# MCP23017_I16_v1_0.net
KiCad netlist of a schematic drawn in EAGLE
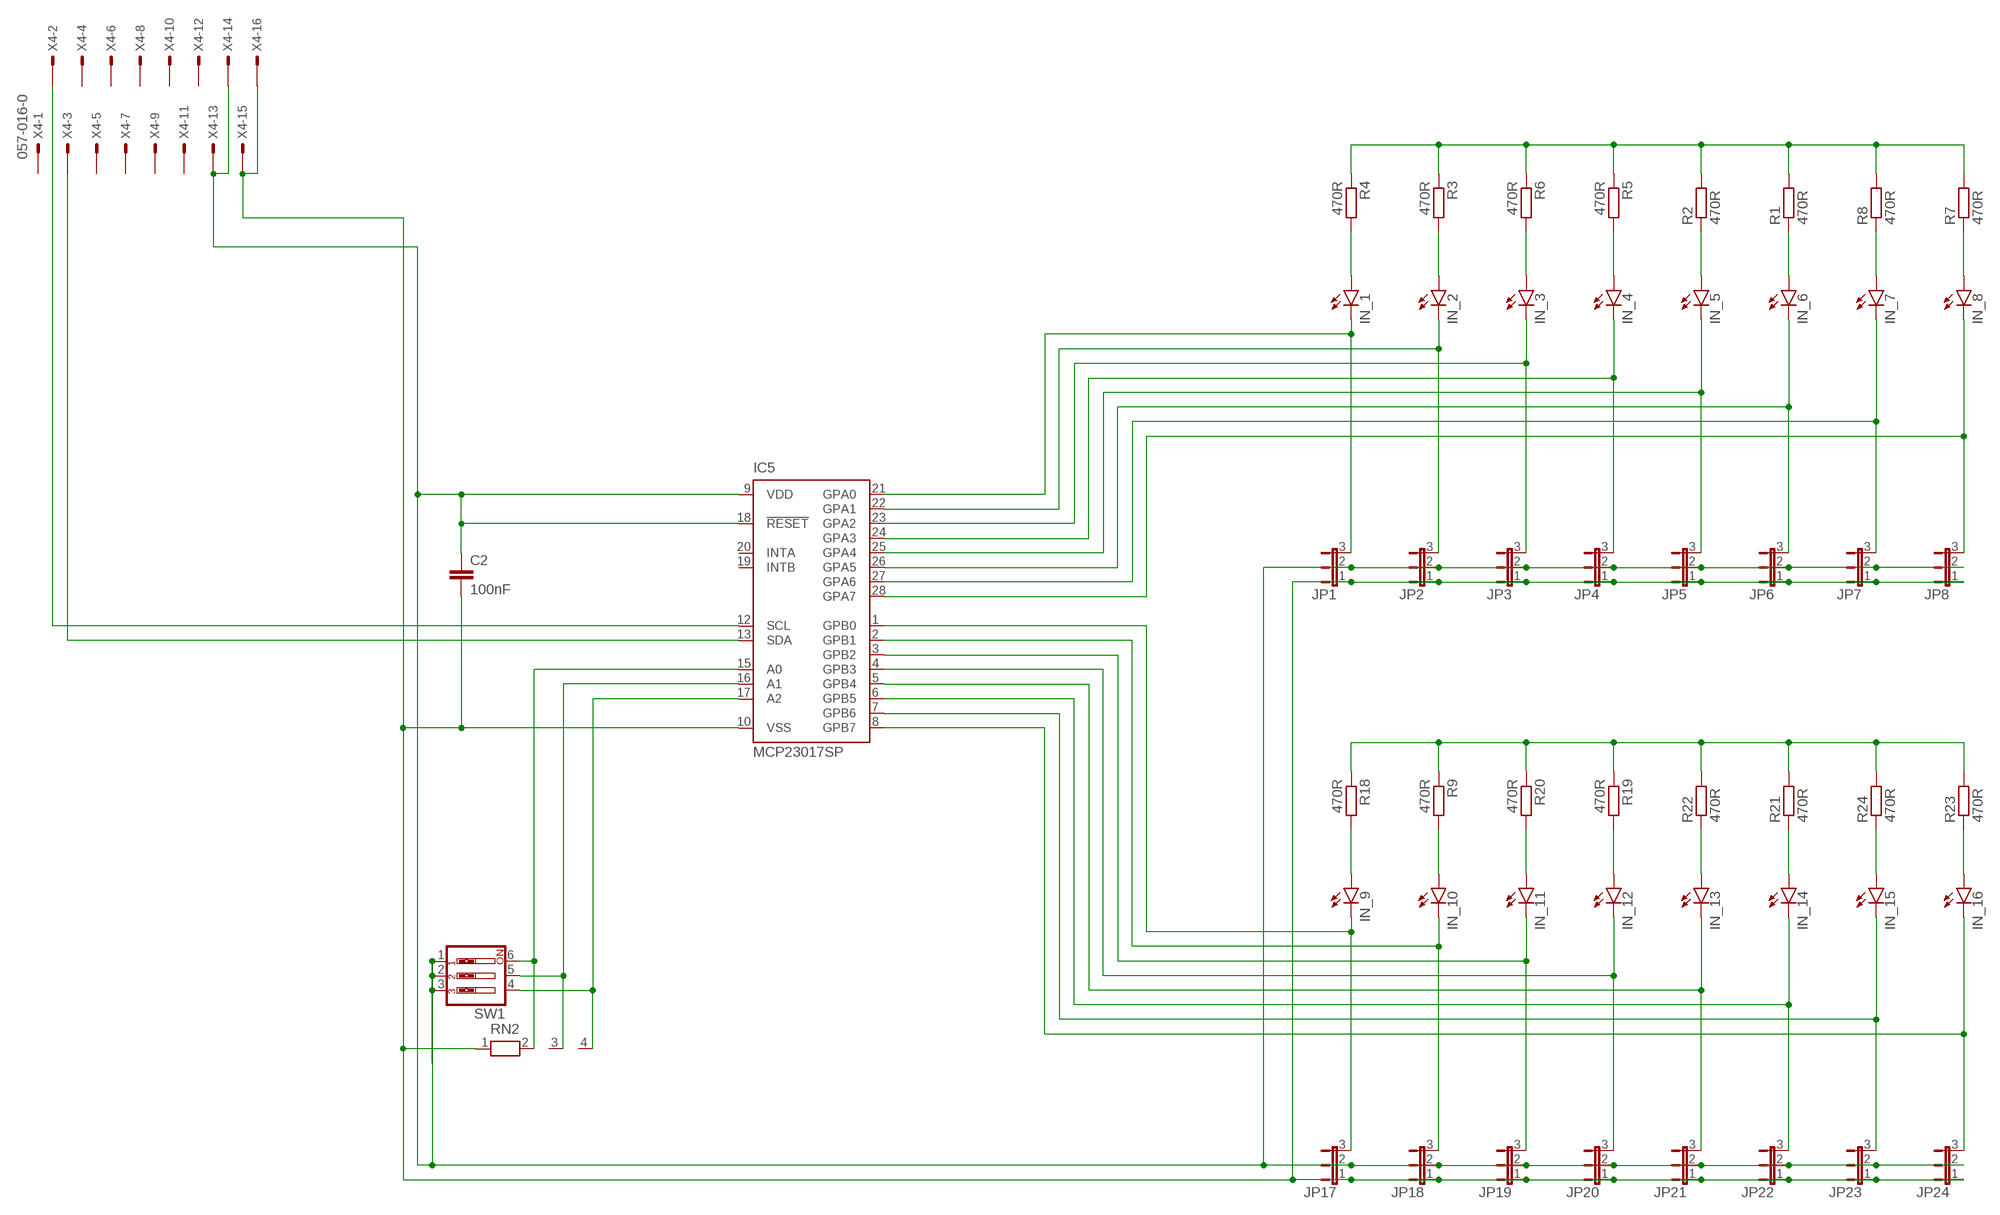
[diagram p0: schematic, sheet 1]

(export (version "E")
  (design (tool "Eeschema 10.0.6"))
  (components
    (comp (ref "C2")
      (value "100nF")
      (footprint "eagle-import:C025-024X044")
      (libsource (lib "eagle-import") (part "C-EU025-024X044"))
    )
    (comp (ref "IC5")
      (value "MCP23017SP")
      (footprint "eagle-import:DIL28-3")
      (libsource (lib "eagle-import") (part "MCP23017SP"))
    )
    (comp (ref "IN_1")
      (value "LED3MM")
      (footprint "eagle-import:LED3MM")
      (libsource (lib "eagle-import") (part "LED3MM"))
    )
    (comp (ref "IN_2")
      (value "LED3MM")
      (footprint "eagle-import:LED3MM")
      (libsource (lib "eagle-import") (part "LED3MM"))
    )
    (comp (ref "IN_3")
      (value "LED3MM")
      (footprint "eagle-import:LED3MM")
      (libsource (lib "eagle-import") (part "LED3MM"))
    )
    (comp (ref "IN_4")
      (value "LED3MM")
      (footprint "eagle-import:LED3MM")
      (libsource (lib "eagle-import") (part "LED3MM"))
    )
    (comp (ref "IN_5")
      (value "LED3MM")
      (footprint "eagle-import:LED3MM")
      (libsource (lib "eagle-import") (part "LED3MM"))
    )
    (comp (ref "IN_6")
      (value "LED3MM")
      (footprint "eagle-import:LED3MM")
      (libsource (lib "eagle-import") (part "LED3MM"))
    )
    (comp (ref "IN_7")
      (value "LED3MM")
      (footprint "eagle-import:LED3MM")
      (libsource (lib "eagle-import") (part "LED3MM"))
    )
    (comp (ref "IN_8")
      (value "LED3MM")
      (footprint "eagle-import:LED3MM")
      (libsource (lib "eagle-import") (part "LED3MM"))
    )
    (comp (ref "IN_9")
      (value "LED3MM")
      (footprint "eagle-import:LED3MM")
      (libsource (lib "eagle-import") (part "LED3MM"))
    )
    (comp (ref "IN_10")
      (value "LED3MM")
      (footprint "eagle-import:LED3MM")
      (libsource (lib "eagle-import") (part "LED3MM"))
    )
    (comp (ref "IN_11")
      (value "LED3MM")
      (footprint "eagle-import:LED3MM")
      (libsource (lib "eagle-import") (part "LED3MM"))
    )
    (comp (ref "IN_12")
      (value "LED3MM")
      (footprint "eagle-import:LED3MM")
      (libsource (lib "eagle-import") (part "LED3MM"))
    )
    (comp (ref "IN_13")
      (value "LED3MM")
      (footprint "eagle-import:LED3MM")
      (libsource (lib "eagle-import") (part "LED3MM"))
    )
    (comp (ref "IN_14")
      (value "LED3MM")
      (footprint "eagle-import:LED3MM")
      (libsource (lib "eagle-import") (part "LED3MM"))
    )
    (comp (ref "IN_15")
      (value "LED3MM")
      (footprint "eagle-import:LED3MM")
      (libsource (lib "eagle-import") (part "LED3MM"))
    )
    (comp (ref "IN_16")
      (value "LED3MM")
      (footprint "eagle-import:LED3MM")
      (libsource (lib "eagle-import") (part "LED3MM"))
    )
    (comp (ref "JP1")
      (value "JP2E")
      (footprint "eagle-import:JP2")
      (libsource (lib "eagle-import") (part "JP2E"))
    )
    (comp (ref "JP2")
      (value "JP2E")
      (footprint "eagle-import:JP2")
      (libsource (lib "eagle-import") (part "JP2E"))
    )
    (comp (ref "JP3")
      (value "JP2E")
      (footprint "eagle-import:JP2")
      (libsource (lib "eagle-import") (part "JP2E"))
    )
    (comp (ref "JP4")
      (value "JP2E")
      (footprint "eagle-import:JP2")
      (libsource (lib "eagle-import") (part "JP2E"))
    )
    (comp (ref "JP5")
      (value "JP2E")
      (footprint "eagle-import:JP2")
      (libsource (lib "eagle-import") (part "JP2E"))
    )
    (comp (ref "JP6")
      (value "JP2E")
      (footprint "eagle-import:JP2")
      (libsource (lib "eagle-import") (part "JP2E"))
    )
    (comp (ref "JP7")
      (value "JP2E")
      (footprint "eagle-import:JP2")
      (libsource (lib "eagle-import") (part "JP2E"))
    )
    (comp (ref "JP8")
      (value "JP2E")
      (footprint "eagle-import:JP2")
      (libsource (lib "eagle-import") (part "JP2E"))
    )
    (comp (ref "JP17")
      (value "JP2E")
      (footprint "eagle-import:JP2")
      (libsource (lib "eagle-import") (part "JP2E"))
    )
    (comp (ref "JP18")
      (value "JP2E")
      (footprint "eagle-import:JP2")
      (libsource (lib "eagle-import") (part "JP2E"))
    )
    (comp (ref "JP19")
      (value "JP2E")
      (footprint "eagle-import:JP2")
      (libsource (lib "eagle-import") (part "JP2E"))
    )
    (comp (ref "JP20")
      (value "JP2E")
      (footprint "eagle-import:JP2")
      (libsource (lib "eagle-import") (part "JP2E"))
    )
    (comp (ref "JP21")
      (value "JP2E")
      (footprint "eagle-import:JP2")
      (libsource (lib "eagle-import") (part "JP2E"))
    )
    (comp (ref "JP22")
      (value "JP2E")
      (footprint "eagle-import:JP2")
      (libsource (lib "eagle-import") (part "JP2E"))
    )
    (comp (ref "JP23")
      (value "JP2E")
      (footprint "eagle-import:JP2")
      (libsource (lib "eagle-import") (part "JP2E"))
    )
    (comp (ref "JP24")
      (value "JP2E")
      (footprint "eagle-import:JP2")
      (libsource (lib "eagle-import") (part "JP2E"))
    )
    (comp (ref "R1")
      (value "470R")
      (footprint "eagle-import:0309_10")
      (libsource (lib "eagle-import") (part "R-EU_0309/10"))
    )
    (comp (ref "R2")
      (value "470R")
      (footprint "eagle-import:0309_10")
      (libsource (lib "eagle-import") (part "R-EU_0309/10"))
    )
    (comp (ref "R3")
      (value "470R")
      (footprint "eagle-import:0309_10")
      (libsource (lib "eagle-import") (part "R-EU_0309/10"))
    )
    (comp (ref "R4")
      (value "470R")
      (footprint "eagle-import:0309_10")
      (libsource (lib "eagle-import") (part "R-EU_0309/10"))
    )
    (comp (ref "R5")
      (value "470R")
      (footprint "eagle-import:0309_10")
      (libsource (lib "eagle-import") (part "R-EU_0309/10"))
    )
    (comp (ref "R6")
      (value "470R")
      (footprint "eagle-import:0309_10")
      (libsource (lib "eagle-import") (part "R-EU_0309/10"))
    )
    (comp (ref "R7")
      (value "470R")
      (footprint "eagle-import:0309_10")
      (libsource (lib "eagle-import") (part "R-EU_0309/10"))
    )
    (comp (ref "R8")
      (value "470R")
      (footprint "eagle-import:0309_10")
      (libsource (lib "eagle-import") (part "R-EU_0309/10"))
    )
    (comp (ref "R9")
      (value "470R")
      (footprint "eagle-import:0309_10")
      (libsource (lib "eagle-import") (part "R-EU_0309/10"))
    )
    (comp (ref "R18")
      (value "470R")
      (footprint "eagle-import:0309_10")
      (libsource (lib "eagle-import") (part "R-EU_0309/10"))
    )
    (comp (ref "R19")
      (value "470R")
      (footprint "eagle-import:0309_10")
      (libsource (lib "eagle-import") (part "R-EU_0309/10"))
    )
    (comp (ref "R20")
      (value "470R")
      (footprint "eagle-import:0309_10")
      (libsource (lib "eagle-import") (part "R-EU_0309/10"))
    )
    (comp (ref "R21")
      (value "470R")
      (footprint "eagle-import:0309_10")
      (libsource (lib "eagle-import") (part "R-EU_0309/10"))
    )
    (comp (ref "R22")
      (value "470R")
      (footprint "eagle-import:0309_10")
      (libsource (lib "eagle-import") (part "R-EU_0309/10"))
    )
    (comp (ref "R23")
      (value "470R")
      (footprint "eagle-import:0309_10")
      (libsource (lib "eagle-import") (part "R-EU_0309/10"))
    )
    (comp (ref "R24")
      (value "470R")
      (footprint "eagle-import:0309_10")
      (libsource (lib "eagle-import") (part "R-EU_0309/10"))
    )
    (comp (ref "RN2")
      (value "RN03")
      (footprint "eagle-import:RN-3")
      (libsource (lib "eagle-import") (part "RN03"))
    )
    (comp (ref "SW1")
      (value "SW_DIP-3")
      (footprint "eagle-import:EDG-03")
      (libsource (lib "eagle-import") (part "SW_DIP-3"))
    )
    (comp (ref "X4")
      (value "057-016-0")
      (footprint "eagle-import:057-016-0")
      (libsource (lib "eagle-import") (part "057-016-0"))
    )
  )
  (nets
    (net (code "1") (name "/VCC5.2") (class "Default")
      (node (ref "C2") (pin "1") (pinfunction "1_1") (pintype "passive"))
      (node (ref "IC5") (pin "18") (pinfunction "~{RESET}_18") (pintype "input"))
      (node (ref "IC5") (pin "9") (pinfunction "VDD_9") (pintype "power_in"))
      (node (ref "JP1") (pin "2") (pinfunction "2_2") (pintype "passive"))
      (node (ref "JP17") (pin "2") (pinfunction "2_2") (pintype "passive"))
      (node (ref "JP18") (pin "2") (pinfunction "2_2") (pintype "passive"))
      (node (ref "JP19") (pin "2") (pinfunction "2_2") (pintype "passive"))
      (node (ref "JP2") (pin "2") (pinfunction "2_2") (pintype "passive"))
      (node (ref "JP20") (pin "2") (pinfunction "2_2") (pintype "passive"))
      (node (ref "JP21") (pin "2") (pinfunction "2_2") (pintype "passive"))
      (node (ref "JP22") (pin "2") (pinfunction "2_2") (pintype "passive"))
      (node (ref "JP23") (pin "2") (pinfunction "2_2") (pintype "passive"))
      (node (ref "JP24") (pin "2") (pinfunction "2_2") (pintype "passive"))
      (node (ref "JP3") (pin "2") (pinfunction "2_2") (pintype "passive"))
      (node (ref "JP4") (pin "2") (pinfunction "2_2") (pintype "passive"))
      (node (ref "JP5") (pin "2") (pinfunction "2_2") (pintype "passive"))
      (node (ref "JP6") (pin "2") (pinfunction "2_2") (pintype "passive"))
      (node (ref "JP7") (pin "2") (pinfunction "2_2") (pintype "passive"))
      (node (ref "JP8") (pin "2") (pinfunction "2_2") (pintype "passive"))
      (node (ref "R1") (pin "2") (pinfunction "2_2") (pintype "passive"))
      (node (ref "R18") (pin "1") (pinfunction "1_1") (pintype "passive"))
      (node (ref "R19") (pin "1") (pinfunction "1_1") (pintype "passive"))
      (node (ref "R2") (pin "2") (pinfunction "2_2") (pintype "passive"))
      (node (ref "R20") (pin "1") (pinfunction "1_1") (pintype "passive"))
      (node (ref "R21") (pin "2") (pinfunction "2_2") (pintype "passive"))
      (node (ref "R22") (pin "2") (pinfunction "2_2") (pintype "passive"))
      (node (ref "R23") (pin "2") (pinfunction "2_2") (pintype "passive"))
      (node (ref "R24") (pin "2") (pinfunction "2_2") (pintype "passive"))
      (node (ref "R3") (pin "1") (pinfunction "1_1") (pintype "passive"))
      (node (ref "R4") (pin "1") (pinfunction "1_1") (pintype "passive"))
      (node (ref "R5") (pin "1") (pinfunction "1_1") (pintype "passive"))
      (node (ref "R6") (pin "1") (pinfunction "1_1") (pintype "passive"))
      (node (ref "R7") (pin "2") (pinfunction "2_2") (pintype "passive"))
      (node (ref "R8") (pin "2") (pinfunction "2_2") (pintype "passive"))
      (node (ref "R9") (pin "1") (pinfunction "1_1") (pintype "passive"))
      (node (ref "SW1") (pin "1") (pinfunction "1_1") (pintype "passive"))
      (node (ref "SW1") (pin "2") (pinfunction "2_2") (pintype "passive"))
      (node (ref "SW1") (pin "3") (pinfunction "3_3") (pintype "passive"))
      (node (ref "X4") (pin "13") (pinfunction "S_13") (pintype "passive"))
      (node (ref "X4") (pin "14") (pinfunction "S_14") (pintype "passive"))
    )
    (net (code "2") (name "Net-(IC5-A0)") (class "Default")
      (node (ref "IC5") (pin "15") (pinfunction "A0_15") (pintype "input"))
      (node (ref "RN2") (pin "2") (pinfunction "2_2") (pintype "passive"))
      (node (ref "SW1") (pin "6") (pinfunction "6_6") (pintype "passive"))
    )
    (net (code "3") (name "Net-(IC5-A1)") (class "Default")
      (node (ref "IC5") (pin "16") (pinfunction "A1_16") (pintype "input"))
      (node (ref "RN2") (pin "3") (pinfunction "3_3") (pintype "passive"))
      (node (ref "SW1") (pin "5") (pinfunction "5_5") (pintype "passive"))
    )
    (net (code "4") (name "Net-(IC5-A2)") (class "Default")
      (node (ref "IC5") (pin "17") (pinfunction "A2_17") (pintype "input"))
      (node (ref "RN2") (pin "4") (pinfunction "4_4") (pintype "passive"))
      (node (ref "SW1") (pin "4") (pinfunction "4_4") (pintype "passive"))
    )
    (net (code "5") (name "Net-(IC5-GPA0)") (class "Default")
      (node (ref "IC5") (pin "21") (pinfunction "GPA0_21") (pintype "bidirectional"))
      (node (ref "IN_1") (pin "K") (pinfunction "C_K") (pintype "passive"))
      (node (ref "JP1") (pin "3") (pinfunction "3_3") (pintype "passive"))
    )
    (net (code "6") (name "Net-(IC5-GPA1)") (class "Default")
      (node (ref "IC5") (pin "22") (pinfunction "GPA1_22") (pintype "bidirectional"))
      (node (ref "IN_2") (pin "K") (pinfunction "C_K") (pintype "passive"))
      (node (ref "JP2") (pin "3") (pinfunction "3_3") (pintype "passive"))
    )
    (net (code "7") (name "Net-(IC5-GPA2)") (class "Default")
      (node (ref "IC5") (pin "23") (pinfunction "GPA2_23") (pintype "bidirectional"))
      (node (ref "IN_3") (pin "K") (pinfunction "C_K") (pintype "passive"))
      (node (ref "JP3") (pin "3") (pinfunction "3_3") (pintype "passive"))
    )
    (net (code "8") (name "Net-(IC5-GPA3)") (class "Default")
      (node (ref "IC5") (pin "24") (pinfunction "GPA3_24") (pintype "bidirectional"))
      (node (ref "IN_4") (pin "K") (pinfunction "C_K") (pintype "passive"))
      (node (ref "JP4") (pin "3") (pinfunction "3_3") (pintype "passive"))
    )
    (net (code "9") (name "Net-(IC5-GPA4)") (class "Default")
      (node (ref "IC5") (pin "25") (pinfunction "GPA4_25") (pintype "bidirectional"))
      (node (ref "IN_5") (pin "K") (pinfunction "C_K") (pintype "passive"))
      (node (ref "JP5") (pin "3") (pinfunction "3_3") (pintype "passive"))
    )
    (net (code "10") (name "Net-(IC5-GPA5)") (class "Default")
      (node (ref "IC5") (pin "26") (pinfunction "GPA5_26") (pintype "bidirectional"))
      (node (ref "IN_6") (pin "K") (pinfunction "C_K") (pintype "passive"))
      (node (ref "JP6") (pin "3") (pinfunction "3_3") (pintype "passive"))
    )
    (net (code "11") (name "Net-(IC5-GPA6)") (class "Default")
      (node (ref "IC5") (pin "27") (pinfunction "GPA6_27") (pintype "bidirectional"))
      (node (ref "IN_7") (pin "K") (pinfunction "C_K") (pintype "passive"))
      (node (ref "JP7") (pin "3") (pinfunction "3_3") (pintype "passive"))
    )
    (net (code "12") (name "Net-(IC5-GPA7)") (class "Default")
      (node (ref "IC5") (pin "28") (pinfunction "GPA7_28") (pintype "bidirectional"))
      (node (ref "IN_8") (pin "K") (pinfunction "C_K") (pintype "passive"))
      (node (ref "JP8") (pin "3") (pinfunction "3_3") (pintype "passive"))
    )
    (net (code "13") (name "Net-(IC5-GPB0)") (class "Default")
      (node (ref "IC5") (pin "1") (pinfunction "GPB0_1") (pintype "bidirectional"))
      (node (ref "IN_9") (pin "K") (pinfunction "C_K") (pintype "passive"))
      (node (ref "JP17") (pin "3") (pinfunction "3_3") (pintype "passive"))
    )
    (net (code "14") (name "Net-(IC5-GPB1)") (class "Default")
      (node (ref "IC5") (pin "2") (pinfunction "GPB1_2") (pintype "bidirectional"))
      (node (ref "IN_10") (pin "K") (pinfunction "C_K") (pintype "passive"))
      (node (ref "JP18") (pin "3") (pinfunction "3_3") (pintype "passive"))
    )
    (net (code "15") (name "Net-(IC5-GPB2)") (class "Default")
      (node (ref "IC5") (pin "3") (pinfunction "GPB2_3") (pintype "bidirectional"))
      (node (ref "IN_11") (pin "K") (pinfunction "C_K") (pintype "passive"))
      (node (ref "JP19") (pin "3") (pinfunction "3_3") (pintype "passive"))
    )
    (net (code "16") (name "Net-(IC5-GPB3)") (class "Default")
      (node (ref "IC5") (pin "4") (pinfunction "GPB3_4") (pintype "bidirectional"))
      (node (ref "IN_12") (pin "K") (pinfunction "C_K") (pintype "passive"))
      (node (ref "JP20") (pin "3") (pinfunction "3_3") (pintype "passive"))
    )
    (net (code "17") (name "Net-(IC5-GPB4)") (class "Default")
      (node (ref "IC5") (pin "5") (pinfunction "GPB4_5") (pintype "bidirectional"))
      (node (ref "IN_13") (pin "K") (pinfunction "C_K") (pintype "passive"))
      (node (ref "JP21") (pin "3") (pinfunction "3_3") (pintype "passive"))
    )
    (net (code "18") (name "Net-(IC5-GPB5)") (class "Default")
      (node (ref "IC5") (pin "6") (pinfunction "GPB5_6") (pintype "bidirectional"))
      (node (ref "IN_14") (pin "K") (pinfunction "C_K") (pintype "passive"))
      (node (ref "JP22") (pin "3") (pinfunction "3_3") (pintype "passive"))
    )
    (net (code "19") (name "Net-(IC5-GPB6)") (class "Default")
      (node (ref "IC5") (pin "7") (pinfunction "GPB6_7") (pintype "bidirectional"))
      (node (ref "IN_15") (pin "K") (pinfunction "C_K") (pintype "passive"))
      (node (ref "JP23") (pin "3") (pinfunction "3_3") (pintype "passive"))
    )
    (net (code "20") (name "Net-(IC5-GPB7)") (class "Default")
      (node (ref "IC5") (pin "8") (pinfunction "GPB7_8") (pintype "bidirectional"))
      (node (ref "IN_16") (pin "K") (pinfunction "C_K") (pintype "passive"))
      (node (ref "JP24") (pin "3") (pinfunction "3_3") (pintype "passive"))
    )
    (net (code "21") (name "Net-(IC5-SCL)") (class "Default")
      (node (ref "IC5") (pin "12") (pinfunction "SCL_12") (pintype "input"))
      (node (ref "X4") (pin "2") (pinfunction "S_2") (pintype "passive"))
    )
    (net (code "22") (name "Net-(IC5-SDA)") (class "Default")
      (node (ref "IC5") (pin "13") (pinfunction "SDA_13") (pintype "bidirectional"))
      (node (ref "X4") (pin "3") (pinfunction "S_3") (pintype "passive"))
    )
    (net (code "23") (name "Net-(IC5-VSS)") (class "Default")
      (node (ref "C2") (pin "2") (pinfunction "2_2") (pintype "passive"))
      (node (ref "IC5") (pin "10") (pinfunction "VSS_10") (pintype "power_in"))
      (node (ref "JP1") (pin "1") (pinfunction "1_1") (pintype "passive"))
      (node (ref "JP17") (pin "1") (pinfunction "1_1") (pintype "passive"))
      (node (ref "JP18") (pin "1") (pinfunction "1_1") (pintype "passive"))
      (node (ref "JP19") (pin "1") (pinfunction "1_1") (pintype "passive"))
      (node (ref "JP2") (pin "1") (pinfunction "1_1") (pintype "passive"))
      (node (ref "JP20") (pin "1") (pinfunction "1_1") (pintype "passive"))
      (node (ref "JP21") (pin "1") (pinfunction "1_1") (pintype "passive"))
      (node (ref "JP22") (pin "1") (pinfunction "1_1") (pintype "passive"))
      (node (ref "JP23") (pin "1") (pinfunction "1_1") (pintype "passive"))
      (node (ref "JP24") (pin "1") (pinfunction "1_1") (pintype "passive"))
      (node (ref "JP3") (pin "1") (pinfunction "1_1") (pintype "passive"))
      (node (ref "JP4") (pin "1") (pinfunction "1_1") (pintype "passive"))
      (node (ref "JP5") (pin "1") (pinfunction "1_1") (pintype "passive"))
      (node (ref "JP6") (pin "1") (pinfunction "1_1") (pintype "passive"))
      (node (ref "JP7") (pin "1") (pinfunction "1_1") (pintype "passive"))
      (node (ref "JP8") (pin "1") (pinfunction "1_1") (pintype "passive"))
      (node (ref "RN2") (pin "1") (pinfunction "1_1") (pintype "passive"))
      (node (ref "X4") (pin "15") (pinfunction "S_15") (pintype "passive"))
      (node (ref "X4") (pin "16") (pinfunction "S_16") (pintype "passive"))
    )
    (net (code "24") (name "Net-(IN_1-PadA)") (class "Default")
      (node (ref "IN_1") (pin "A") (pinfunction "A_A") (pintype "passive"))
      (node (ref "R4") (pin "2") (pinfunction "2_2") (pintype "passive"))
    )
    (net (code "25") (name "Net-(IN_2-PadA)") (class "Default")
      (node (ref "IN_2") (pin "A") (pinfunction "A_A") (pintype "passive"))
      (node (ref "R3") (pin "2") (pinfunction "2_2") (pintype "passive"))
    )
    (net (code "26") (name "Net-(IN_3-PadA)") (class "Default")
      (node (ref "IN_3") (pin "A") (pinfunction "A_A") (pintype "passive"))
      (node (ref "R6") (pin "2") (pinfunction "2_2") (pintype "passive"))
    )
    (net (code "27") (name "Net-(IN_4-PadA)") (class "Default")
      (node (ref "IN_4") (pin "A") (pinfunction "A_A") (pintype "passive"))
      (node (ref "R5") (pin "2") (pinfunction "2_2") (pintype "passive"))
    )
    (net (code "28") (name "Net-(IN_5-PadA)") (class "Default")
      (node (ref "IN_5") (pin "A") (pinfunction "A_A") (pintype "passive"))
      (node (ref "R2") (pin "1") (pinfunction "1_1") (pintype "passive"))
    )
    (net (code "29") (name "Net-(IN_6-PadA)") (class "Default")
      (node (ref "IN_6") (pin "A") (pinfunction "A_A") (pintype "passive"))
      (node (ref "R1") (pin "1") (pinfunction "1_1") (pintype "passive"))
    )
    (net (code "30") (name "Net-(IN_7-PadA)") (class "Default")
      (node (ref "IN_7") (pin "A") (pinfunction "A_A") (pintype "passive"))
      (node (ref "R8") (pin "1") (pinfunction "1_1") (pintype "passive"))
    )
    (net (code "31") (name "Net-(IN_8-PadA)") (class "Default")
      (node (ref "IN_8") (pin "A") (pinfunction "A_A") (pintype "passive"))
      (node (ref "R7") (pin "1") (pinfunction "1_1") (pintype "passive"))
    )
    (net (code "32") (name "Net-(IN_9-PadA)") (class "Default")
      (node (ref "IN_9") (pin "A") (pinfunction "A_A") (pintype "passive"))
      (node (ref "R18") (pin "2") (pinfunction "2_2") (pintype "passive"))
    )
    (net (code "33") (name "Net-(IN_10-PadA)") (class "Default")
      (node (ref "IN_10") (pin "A") (pinfunction "A_A") (pintype "passive"))
      (node (ref "R9") (pin "2") (pinfunction "2_2") (pintype "passive"))
    )
    (net (code "34") (name "Net-(IN_11-PadA)") (class "Default")
      (node (ref "IN_11") (pin "A") (pinfunction "A_A") (pintype "passive"))
      (node (ref "R20") (pin "2") (pinfunction "2_2") (pintype "passive"))
    )
    (net (code "35") (name "Net-(IN_12-PadA)") (class "Default")
      (node (ref "IN_12") (pin "A") (pinfunction "A_A") (pintype "passive"))
      (node (ref "R19") (pin "2") (pinfunction "2_2") (pintype "passive"))
    )
    (net (code "36") (name "Net-(IN_13-PadA)") (class "Default")
      (node (ref "IN_13") (pin "A") (pinfunction "A_A") (pintype "passive"))
      (node (ref "R22") (pin "1") (pinfunction "1_1") (pintype "passive"))
    )
    (net (code "37") (name "Net-(IN_14-PadA)") (class "Default")
      (node (ref "IN_14") (pin "A") (pinfunction "A_A") (pintype "passive"))
      (node (ref "R21") (pin "1") (pinfunction "1_1") (pintype "passive"))
    )
    (net (code "38") (name "Net-(IN_15-PadA)") (class "Default")
      (node (ref "IN_15") (pin "A") (pinfunction "A_A") (pintype "passive"))
      (node (ref "R24") (pin "1") (pinfunction "1_1") (pintype "passive"))
    )
    (net (code "39") (name "Net-(IN_16-PadA)") (class "Default")
      (node (ref "IN_16") (pin "A") (pinfunction "A_A") (pintype "passive"))
      (node (ref "R23") (pin "1") (pinfunction "1_1") (pintype "passive"))
    )
    (net (code "40") (name "unconnected-(IC5-INTA-Pad20)") (class "Default")
      (node (ref "IC5") (pin "20") (pinfunction "INTA_20") (pintype "output"))
    )
    (net (code "41") (name "unconnected-(IC5-INTB-Pad19)") (class "Default")
      (node (ref "IC5") (pin "19") (pinfunction "INTB_19") (pintype "output"))
    )
    (net (code "42") (name "unconnected-(X4A-S-Pad1)") (class "Default")
      (node (ref "X4") (pin "1") (pinfunction "S_1") (pintype "passive"))
    )
    (net (code "43") (name "unconnected-(X4B-S-Pad10)") (class "Default")
      (node (ref "X4") (pin "10") (pinfunction "S_10") (pintype "passive"))
    )
    (net (code "44") (name "unconnected-(X4C-S-Pad11)") (class "Default")
      (node (ref "X4") (pin "11") (pinfunction "S_11") (pintype "passive"))
    )
    (net (code "45") (name "unconnected-(X4D-S-Pad12)") (class "Default")
      (node (ref "X4") (pin "12") (pinfunction "S_12") (pintype "passive"))
    )
    (net (code "46") (name "unconnected-(X4K-S-Pad4)") (class "Default")
      (node (ref "X4") (pin "4") (pinfunction "S_4") (pintype "passive"))
    )
    (net (code "47") (name "unconnected-(X4L-S-Pad5)") (class "Default")
      (node (ref "X4") (pin "5") (pinfunction "S_5") (pintype "passive"))
    )
    (net (code "48") (name "unconnected-(X4M-S-Pad6)") (class "Default")
      (node (ref "X4") (pin "6") (pinfunction "S_6") (pintype "passive"))
    )
    (net (code "49") (name "unconnected-(X4N-S-Pad7)") (class "Default")
      (node (ref "X4") (pin "7") (pinfunction "S_7") (pintype "passive"))
    )
    (net (code "50") (name "unconnected-(X4O-S-Pad8)") (class "Default")
      (node (ref "X4") (pin "8") (pinfunction "S_8") (pintype "passive"))
    )
    (net (code "51") (name "unconnected-(X4P-S-Pad9)") (class "Default")
      (node (ref "X4") (pin "9") (pinfunction "S_9") (pintype "passive"))
    )
  )
)
